# OLED_DISPLAY.net
KiCad netlist of a schematic drawn in Altium Designer
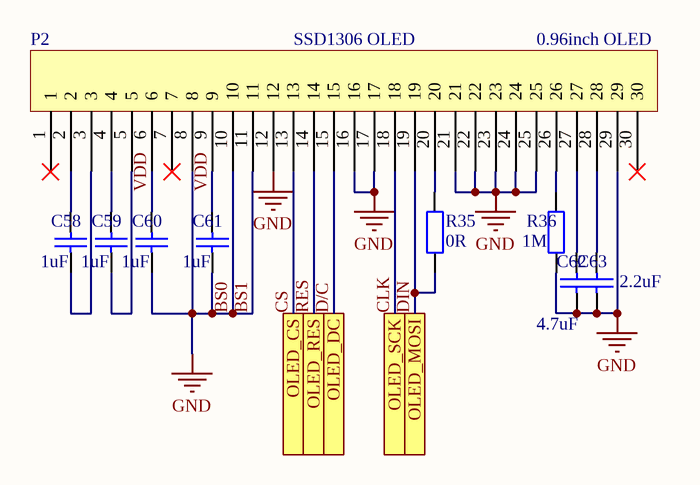
[diagram p0: OLED_DISPLAY.SchDoc]

(export (version "E")
  (design (tool "Eeschema 10.0.6"))
  (components
    (comp (ref "C58")
      (value "1uF")
      (footprint "0603_CAP_NPOL")
      (description "Capacitor")
      (fields (field (name "Comment") "Cap") (field (name "PUBLISHER") "Altium Limited"))
      (libsource (lib "Miscellaneous Devices") (part "Cap"))
    )
    (comp (ref "C59")
      (value "1uF")
      (footprint "0603_CAP_NPOL")
      (description "Capacitor")
      (fields (field (name "Comment") "Cap") (field (name "PUBLISHER") "Altium Limited"))
      (libsource (lib "Miscellaneous Devices") (part "Cap"))
    )
    (comp (ref "C60")
      (value "1uF")
      (footprint "0603_CAP_NPOL")
      (description "Capacitor")
      (fields (field (name "Comment") "Cap") (field (name "PUBLISHER") "Altium Limited"))
      (libsource (lib "Miscellaneous Devices") (part "Cap"))
    )
    (comp (ref "C61")
      (value "1uF")
      (footprint "0603_CAP_NPOL")
      (description "Capacitor")
      (fields (field (name "Comment") "Cap") (field (name "PUBLISHER") "Altium Limited"))
      (libsource (lib "Miscellaneous Devices") (part "Cap"))
    )
    (comp (ref "C62")
      (value "4.7uF")
      (footprint "0603_CAP_NPOL")
      (description "Capacitor")
      (fields (field (name "Comment") "Cap") (field (name "PUBLISHER") "Altium Limited"))
      (libsource (lib "Miscellaneous Devices") (part "Cap"))
    )
    (comp (ref "C63")
      (value "2.2uF")
      (footprint "0603_CAP_NPOL")
      (description "Capacitor")
      (fields (field (name "Comment") "Cap") (field (name "PUBLISHER") "Altium Limited"))
      (libsource (lib "Miscellaneous Devices") (part "Cap"))
    )
    (comp (ref "P2")
      (value "0.96inch OLED")
      (footprint "SSD1306_OLED")
      (fields (field (name "NAME") "SSD1306 OLED"))
      (libsource (lib "schematy") (part "SSD1306 OLED"))
    )
    (comp (ref "R35")
      (value "0R")
      (footprint "0402_RES")
      (description "Resistor")
      (fields (field (name "Comment") "Res2") (field (name "PUBLISHER") "Altium Limited"))
      (libsource (lib "Miscellaneous Devices") (part "Res2"))
    )
    (comp (ref "R36")
      (value "1M")
      (footprint "0402_RES")
      (description "Resistor")
      (fields (field (name "Comment") "Res2") (field (name "PUBLISHER") "Altium Limited"))
      (libsource (lib "Miscellaneous Devices") (part "Res2"))
    )
  )
  (nets
    (net (code "1") (name "/CLK") (class "Default")
      (node (ref "P2") (pin "18") (pinfunction "18_18") (pintype "passive"))
    )
    (net (code "2") (name "/CS") (class "Default")
      (node (ref "P2") (pin "13") (pinfunction "13_13") (pintype "passive"))
    )
    (net (code "3") (name "/DIN") (class "Default")
      (node (ref "P2") (pin "19") (pinfunction "19_19") (pintype "passive"))
      (node (ref "R35") (pin "1") (pinfunction "1_1") (pintype "passive"))
    )
    (net (code "4") (name "/D{slash}C") (class "Default")
      (node (ref "P2") (pin "15") (pinfunction "15_15") (pintype "passive"))
    )
    (net (code "5") (name "/RES") (class "Default")
      (node (ref "P2") (pin "14") (pinfunction "14_14") (pintype "passive"))
    )
    (net (code "6") (name "/VDD") (class "Default")
      (node (ref "C60") (pin "2") (pinfunction "2_2") (pintype "passive"))
      (node (ref "C61") (pin "2") (pinfunction "2_2") (pintype "passive"))
      (node (ref "P2") (pin "6") (pinfunction "6_6") (pintype "passive"))
      (node (ref "P2") (pin "9") (pinfunction "9_9") (pintype "passive"))
    )
    (net (code "7") (name "GND") (class "Default")
      (node (ref "C60") (pin "1") (pinfunction "1_1") (pintype "passive"))
      (node (ref "C61") (pin "1") (pinfunction "1_1") (pintype "passive"))
      (node (ref "C62") (pin "1") (pinfunction "1_1") (pintype "passive"))
      (node (ref "C63") (pin "1") (pinfunction "1_1") (pintype "passive"))
      (node (ref "P2") (pin "10") (pinfunction "10_10") (pintype "passive"))
      (node (ref "P2") (pin "11") (pinfunction "11_11") (pintype "passive"))
      (node (ref "P2") (pin "12") (pinfunction "12_12") (pintype "passive"))
      (node (ref "P2") (pin "16") (pinfunction "16_16") (pintype "passive"))
      (node (ref "P2") (pin "17") (pinfunction "17_17") (pintype "passive"))
      (node (ref "P2") (pin "21") (pinfunction "21_21") (pintype "passive"))
      (node (ref "P2") (pin "22") (pinfunction "22_22") (pintype "passive"))
      (node (ref "P2") (pin "23") (pinfunction "23_23") (pintype "passive"))
      (node (ref "P2") (pin "24") (pinfunction "24_24") (pintype "passive"))
      (node (ref "P2") (pin "25") (pinfunction "25_25") (pintype "passive"))
      (node (ref "P2") (pin "29") (pinfunction "29_29") (pintype "passive"))
      (node (ref "P2") (pin "8") (pinfunction "8_8") (pintype "passive"))
      (node (ref "R36") (pin "1") (pinfunction "1_1") (pintype "passive"))
    )
    (net (code "8") (name "Net-(C58-Pad1)") (class "Default")
      (node (ref "C58") (pin "1") (pinfunction "1_1") (pintype "passive"))
      (node (ref "P2") (pin "3") (pinfunction "3_3") (pintype "passive"))
    )
    (net (code "9") (name "Net-(C58-Pad2)") (class "Default")
      (node (ref "C58") (pin "2") (pinfunction "2_2") (pintype "passive"))
      (node (ref "P2") (pin "2") (pinfunction "2_2") (pintype "passive"))
    )
    (net (code "10") (name "Net-(C59-Pad1)") (class "Default")
      (node (ref "C59") (pin "1") (pinfunction "1_1") (pintype "passive"))
      (node (ref "P2") (pin "5") (pinfunction "5_5") (pintype "passive"))
    )
    (net (code "11") (name "Net-(C59-Pad2)") (class "Default")
      (node (ref "C59") (pin "2") (pinfunction "2_2") (pintype "passive"))
      (node (ref "P2") (pin "4") (pinfunction "4_4") (pintype "passive"))
    )
    (net (code "12") (name "Net-(C62-Pad2)") (class "Default")
      (node (ref "C62") (pin "2") (pinfunction "2_2") (pintype "passive"))
      (node (ref "P2") (pin "27") (pinfunction "27_27") (pintype "passive"))
    )
    (net (code "13") (name "Net-(C63-Pad2)") (class "Default")
      (node (ref "C63") (pin "2") (pinfunction "2_2") (pintype "passive"))
      (node (ref "P2") (pin "28") (pinfunction "28_28") (pintype "passive"))
    )
    (net (code "14") (name "Net-(P2-Pad20)") (class "Default")
      (node (ref "P2") (pin "20") (pinfunction "20_20") (pintype "passive"))
      (node (ref "R35") (pin "2") (pinfunction "2_2") (pintype "passive"))
    )
    (net (code "15") (name "Net-(P2-Pad26)") (class "Default")
      (node (ref "P2") (pin "26") (pinfunction "26_26") (pintype "passive"))
      (node (ref "R36") (pin "2") (pinfunction "2_2") (pintype "passive"))
    )
    (net (code "16") (name "unconnected-(P2-Pad1)") (class "Default")
      (node (ref "P2") (pin "1") (pinfunction "1_1") (pintype "passive+no_connect"))
    )
    (net (code "17") (name "unconnected-(P2-Pad7)") (class "Default")
      (node (ref "P2") (pin "7") (pinfunction "7_7") (pintype "passive+no_connect"))
    )
    (net (code "18") (name "unconnected-(P2-Pad30)") (class "Default")
      (node (ref "P2") (pin "30") (pinfunction "30_30") (pintype "passive+no_connect"))
    )
  )
)
